# Board_V04.net
KiCad netlist of a schematic drawn in EAGLE
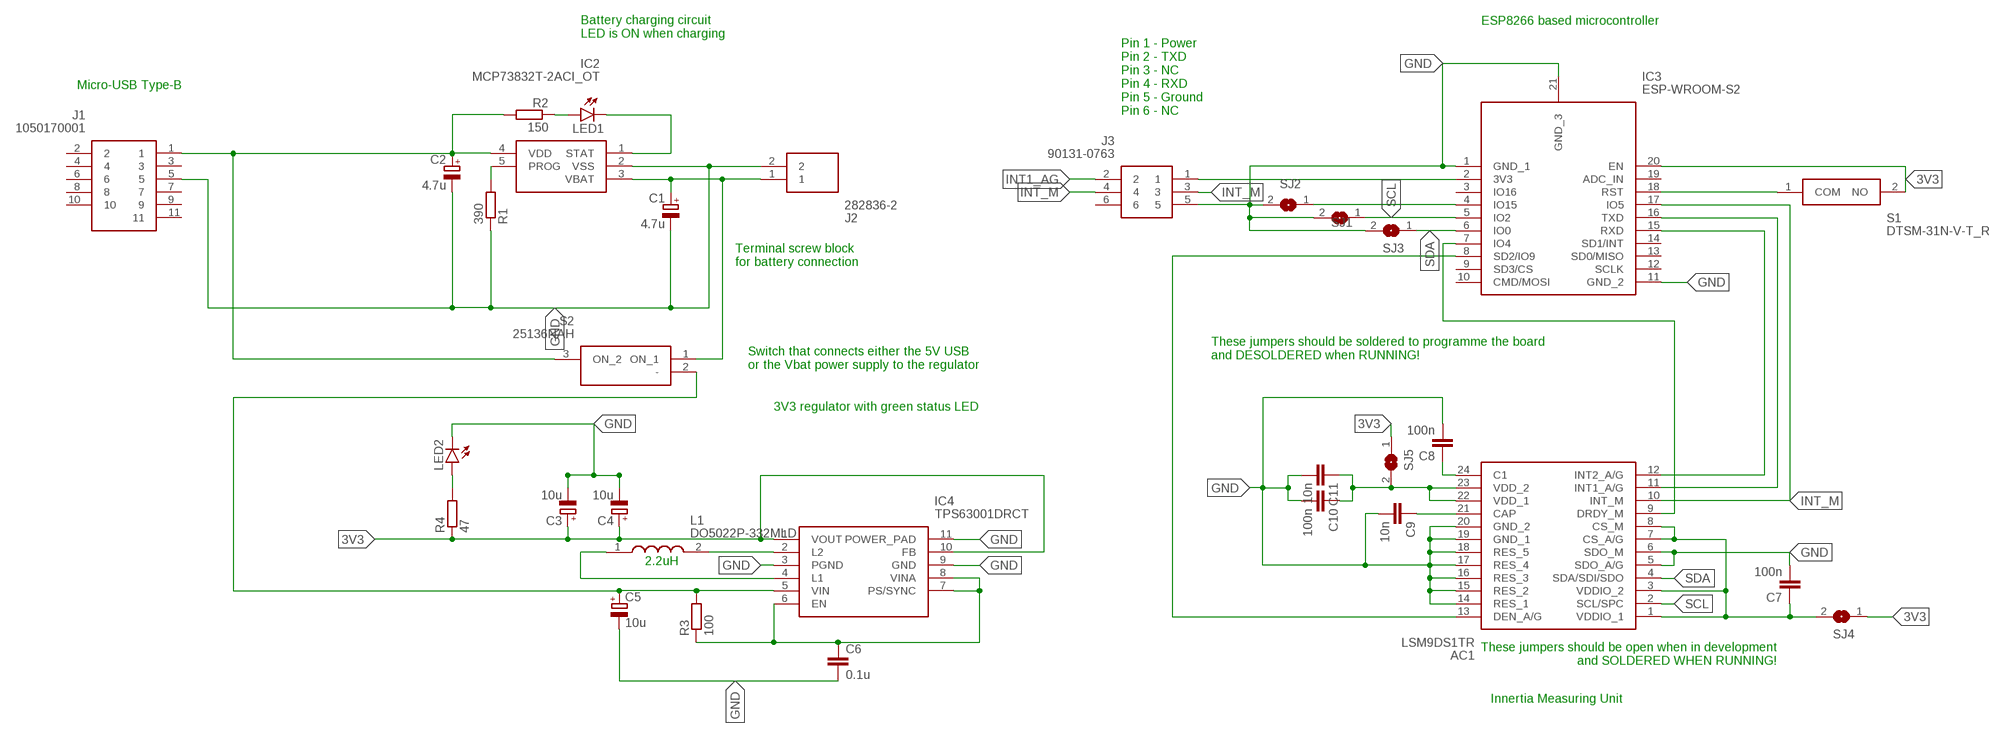
[diagram p0: schematic, sheet 1]

(export (version "E")
  (design (tool "Eeschema 10.0.6"))
  (components
    (comp (ref "AC1")
      (value "LSM9DS1TR")
      (footprint "eagle-import:LGA-24L(3X3.5X1MM)")
      (fields (field (name "MOUSER_PART_NUMBER") "511-LSM9DS1TR") (field (name "RS_PART_NUMBER") "1660908"))
      (libsource (lib "eagle-import") (part "LSM9DS1TR"))
    )
    (comp (ref "C1")
      (value "4.7u")
      (footprint "eagle-import:D_7343-31R")
      (libsource (lib "eagle-import") (part "CPOL-EUD/7343-31R"))
    )
    (comp (ref "C2")
      (value "4.7u")
      (footprint "eagle-import:D_7343-31R")
      (libsource (lib "eagle-import") (part "CPOL-EUD/7343-31R"))
    )
    (comp (ref "C3")
      (value "10u")
      (footprint "eagle-import:D_7343-31R")
      (libsource (lib "eagle-import") (part "CPOL-EUD/7343-31R"))
    )
    (comp (ref "C4")
      (value "10u")
      (footprint "eagle-import:D_7343-31R")
      (libsource (lib "eagle-import") (part "CPOL-EUD/7343-31R"))
    )
    (comp (ref "C5")
      (value "10u")
      (footprint "eagle-import:D_7343-31R")
      (libsource (lib "eagle-import") (part "CPOL-EUD/7343-31R"))
    )
    (comp (ref "C6")
      (value "0.1u")
      (footprint "eagle-import:C0402")
      (libsource (lib "eagle-import") (part "C-EUC0402"))
    )
    (comp (ref "C7")
      (value "100n")
      (footprint "eagle-import:C0805")
      (libsource (lib "eagle-import") (part "C-EUC0805"))
    )
    (comp (ref "C8")
      (value "100n")
      (footprint "eagle-import:C0805")
      (libsource (lib "eagle-import") (part "C-EUC0805"))
    )
    (comp (ref "C9")
      (value "10n")
      (footprint "eagle-import:C0805")
      (libsource (lib "eagle-import") (part "C-EUC0805"))
    )
    (comp (ref "C10")
      (value "100n")
      (footprint "eagle-import:C0805")
      (libsource (lib "eagle-import") (part "C-EUC0805"))
    )
    (comp (ref "C11")
      (value "10n")
      (footprint "eagle-import:C0805")
      (libsource (lib "eagle-import") (part "C-EUC0805"))
    )
    (comp (ref "IC2")
      (value "MCP73832T-2ACI_OT")
      (footprint "eagle-import:SOT95P270X145-5N")
      (fields
        (field (name "MANUFACTURER_PART_NUMBER") "MCP73832T-2ACI/OT")
        (field (name "MOUSER_PART_NUMBER") "579-MCP73832T-2ACIOT")
        (field (name "RS_PART_NUMBER") "9122897")
      )
      (libsource (lib "eagle-import") (part "MCP73832T-2ACI_OT"))
    )
    (comp (ref "IC3")
      (value "ESP-WROOM-S2")
      (footprint "eagle-import:QFN150P1600X1700X315-21N")
      (libsource (lib "eagle-import") (part "ESP-WROOM-S2"))
    )
    (comp (ref "IC4")
      (value "TPS63001DRCT")
      (footprint "eagle-import:SON50P300X300X100-11N")
      (fields (field (name "RS_PART_NUMBER") "7968405"))
      (libsource (lib "eagle-import") (part "TPS63001DRCT"))
    )
    (comp (ref "J1")
      (value "1050170001")
      (footprint "eagle-import:MICROUSB-BTYPE")
      (libsource (lib "eagle-import") (part "1050170001"))
    )
    (comp (ref "J2")
      (value "282836-2")
      (footprint "eagle-import:SHDR2W100P0X500_1X2_1000X820X1")
      (fields (field (name "MOUSER_PART_NUMBER") "571-2828362") (field (name "RS_PART_NUMBER") "1354983"))
      (libsource (lib "eagle-import") (part "282836-2"))
    )
    (comp (ref "J3")
      (value "90131-0763")
      (footprint "eagle-import:HDRV6W90P254_2X3_762X500X560P")
      (fields (field (name "MOUSER_PART_NUMBER") "538-90131-0763") (field (name "RS_PART_NUMBER") "3606443P"))
      (libsource (lib "eagle-import") (part "90131-0763"))
    )
    (comp (ref "L1")
      (value "DO5022P-332MLD")
      (footprint "eagle-import:DO5022P-104MLD")
      (fields (field (name "MOUSER_PART_NUMBER") "994-DO5022P-332MLD"))
      (libsource (lib "eagle-import") (part "DO5022P-332MLD"))
    )
    (comp (ref "LED1")
      (value "LED5MM")
      (footprint "eagle-import:LED5MM")
      (libsource (lib "eagle-import") (part "LED5MM"))
    )
    (comp (ref "LED2")
      (value "LED5MM")
      (footprint "eagle-import:LED5MM")
      (libsource (lib "eagle-import") (part "LED5MM"))
    )
    (comp (ref "R1")
      (value "390")
      (footprint "eagle-import:R0805")
      (libsource (lib "eagle-import") (part "R-EU_R0805"))
    )
    (comp (ref "R2")
      (value "150")
      (footprint "eagle-import:R0805")
      (libsource (lib "eagle-import") (part "R-EU_R0805"))
    )
    (comp (ref "R3")
      (value "100")
      (footprint "eagle-import:R0805")
      (libsource (lib "eagle-import") (part "R-EU_R0805"))
    )
    (comp (ref "R4")
      (value "47")
      (footprint "eagle-import:R0805")
      (libsource (lib "eagle-import") (part "R-EU_R0805"))
    )
    (comp (ref "S1")
      (value "DTSM-31N-V-T_R")
      (footprint "eagle-import:DTSM32NVTR")
      (fields
        (field (name "MANUFACTURER_PART_NUMBER") "DTSM-31N-V-T/R")
        (field (name "MOUSER_PART_NUMBER") "113-DTSM31NVTR")
      )
      (libsource (lib "eagle-import") (part "DTSM-31N-V-T_R"))
    )
    (comp (ref "S2")
      (value "25136NAH")
      (footprint "eagle-import:25136NAH")
      (fields (field (name "MOUSER_PART_NUMBER") "642-25136NAH") (field (name "RS_PART_NUMBER") "0339673A"))
      (libsource (lib "eagle-import") (part "25136NAH"))
    )
    (comp (ref "SJ1")
      (value "SJW")
      (footprint "eagle-import:SJW")
      (libsource (lib "eagle-import") (part "SJW"))
    )
    (comp (ref "SJ2")
      (value "SJW")
      (footprint "eagle-import:SJW")
      (libsource (lib "eagle-import") (part "SJW"))
    )
    (comp (ref "SJ3")
      (value "SJW")
      (footprint "eagle-import:SJW")
      (libsource (lib "eagle-import") (part "SJW"))
    )
    (comp (ref "SJ4")
      (value "SJW")
      (footprint "eagle-import:SJW")
      (libsource (lib "eagle-import") (part "SJW"))
    )
    (comp (ref "SJ5")
      (value "SJW")
      (footprint "eagle-import:SJW")
      (libsource (lib "eagle-import") (part "SJW"))
    )
  )
  (nets
    (net (code "1") (name "3V3") (class "Default")
      (node (ref "C3") (pin "+") (pinfunction "+_+") (pintype "passive"))
      (node (ref "C4") (pin "+") (pinfunction "+_+") (pintype "passive"))
      (node (ref "IC3") (pin "2") (pinfunction "3V3_2") (pintype "power_in"))
      (node (ref "IC3") (pin "20") (pinfunction "EN_20") (pintype "bidirectional"))
      (node (ref "IC4") (pin "1") (pinfunction "VOUT_1") (pintype "bidirectional"))
      (node (ref "IC4") (pin "10") (pinfunction "FB_10") (pintype "bidirectional"))
      (node (ref "J3") (pin "1") (pinfunction "1_1") (pintype "bidirectional"))
      (node (ref "R4") (pin "1") (pinfunction "1_1") (pintype "passive"))
      (node (ref "S1") (pin "2") (pinfunction "NO_2") (pintype "bidirectional"))
      (node (ref "SJ4") (pin "1") (pinfunction "1_1") (pintype "passive"))
      (node (ref "SJ5") (pin "1") (pinfunction "1_1") (pintype "passive"))
    )
    (net (code "2") (name "GND") (class "Default")
      (node (ref "AC1") (pin "14") (pinfunction "RES_1_14") (pintype "power_in"))
      (node (ref "AC1") (pin "15") (pinfunction "RES_2_15") (pintype "power_in"))
      (node (ref "AC1") (pin "16") (pinfunction "RES_3_16") (pintype "power_in"))
      (node (ref "AC1") (pin "17") (pinfunction "RES_4_17") (pintype "power_in"))
      (node (ref "AC1") (pin "18") (pinfunction "RES_5_18") (pintype "power_in"))
      (node (ref "AC1") (pin "19") (pinfunction "GND_1_19") (pintype "power_in"))
      (node (ref "AC1") (pin "20") (pinfunction "GND_2_20") (pintype "power_in"))
      (node (ref "AC1") (pin "5") (pinfunction "SDO_A/G_5") (pintype "output"))
      (node (ref "AC1") (pin "6") (pinfunction "SDO_M_6") (pintype "output"))
      (node (ref "C1") (pin "-") (pinfunction "-_-") (pintype "passive"))
      (node (ref "C10") (pin "2") (pinfunction "2_2") (pintype "passive"))
      (node (ref "C11") (pin "2") (pinfunction "2_2") (pintype "passive"))
      (node (ref "C2") (pin "-") (pinfunction "-_-") (pintype "passive"))
      (node (ref "C3") (pin "-") (pinfunction "-_-") (pintype "passive"))
      (node (ref "C4") (pin "-") (pinfunction "-_-") (pintype "passive"))
      (node (ref "C5") (pin "-") (pinfunction "-_-") (pintype "passive"))
      (node (ref "C6") (pin "2") (pinfunction "2_2") (pintype "passive"))
      (node (ref "C7") (pin "2") (pinfunction "2_2") (pintype "passive"))
      (node (ref "C8") (pin "2") (pinfunction "2_2") (pintype "passive"))
      (node (ref "C9") (pin "2") (pinfunction "2_2") (pintype "passive"))
      (node (ref "IC2") (pin "2") (pinfunction "VSS_2") (pintype "power_in"))
      (node (ref "IC3") (pin "1") (pinfunction "GND_1_1") (pintype "power_in"))
      (node (ref "IC3") (pin "11") (pinfunction "GND_2_11") (pintype "power_in"))
      (node (ref "IC3") (pin "21") (pinfunction "GND_3_21") (pintype "power_in"))
      (node (ref "IC4") (pin "11") (pinfunction "POWER_PAD_11") (pintype "bidirectional"))
      (node (ref "IC4") (pin "3") (pinfunction "PGND_3") (pintype "bidirectional"))
      (node (ref "IC4") (pin "9") (pinfunction "GND_9") (pintype "bidirectional"))
      (node (ref "J1") (pin "5") (pinfunction "5_5") (pintype "bidirectional"))
      (node (ref "J2") (pin "2") (pinfunction "2_2") (pintype "bidirectional"))
      (node (ref "J3") (pin "5") (pinfunction "5_5") (pintype "bidirectional"))
      (node (ref "LED2") (pin "K") (pinfunction "C_K") (pintype "passive"))
      (node (ref "R1") (pin "1") (pinfunction "1_1") (pintype "passive"))
      (node (ref "SJ1") (pin "2") (pinfunction "2_2") (pintype "passive"))
      (node (ref "SJ2") (pin "2") (pinfunction "2_2") (pintype "passive"))
      (node (ref "SJ3") (pin "2") (pinfunction "2_2") (pintype "passive"))
    )
    (net (code "3") (name "INT1_AG") (class "Default")
      (node (ref "AC1") (pin "11") (pinfunction "INT1_A/G_11") (pintype "bidirectional"))
      (node (ref "IC3") (pin "16") (pinfunction "TXD_16") (pintype "bidirectional"))
      (node (ref "J3") (pin "2") (pinfunction "2_2") (pintype "bidirectional"))
    )
    (net (code "4") (name "INT_M") (class "Default")
      (node (ref "AC1") (pin "10") (pinfunction "INT_M_10") (pintype "bidirectional"))
      (node (ref "IC3") (pin "17") (pinfunction "IO5_17") (pintype "bidirectional"))
      (node (ref "J3") (pin "3") (pinfunction "3_3") (pintype "bidirectional"))
      (node (ref "J3") (pin "4") (pinfunction "4_4") (pintype "bidirectional"))
    )
    (net (code "5") (name "Net-(AC1-C1)") (class "Default")
      (node (ref "AC1") (pin "24") (pinfunction "C1_24") (pintype "bidirectional"))
      (node (ref "C8") (pin "1") (pinfunction "1_1") (pintype "passive"))
    )
    (net (code "6") (name "Net-(AC1-CAP)") (class "Default")
      (node (ref "AC1") (pin "21") (pinfunction "CAP_21") (pintype "power_in"))
      (node (ref "C9") (pin "1") (pinfunction "1_1") (pintype "passive"))
    )
    (net (code "7") (name "Net-(AC1-CS_A{slash}G)") (class "Default")
      (node (ref "AC1") (pin "1") (pinfunction "VDDIO_1_1") (pintype "power_in"))
      (node (ref "AC1") (pin "3") (pinfunction "VDDIO_2_3") (pintype "power_in"))
      (node (ref "AC1") (pin "7") (pinfunction "CS_A/G_7") (pintype "bidirectional"))
      (node (ref "AC1") (pin "8") (pinfunction "CS_M_8") (pintype "bidirectional"))
      (node (ref "C7") (pin "1") (pinfunction "1_1") (pintype "passive"))
      (node (ref "SJ4") (pin "2") (pinfunction "2_2") (pintype "passive"))
    )
    (net (code "8") (name "Net-(AC1-DEN_A{slash}G)") (class "Default")
      (node (ref "AC1") (pin "13") (pinfunction "DEN_A/G_13") (pintype "bidirectional"))
      (node (ref "IC3") (pin "8") (pinfunction "SD2/IO9_8") (pintype "bidirectional"))
    )
    (net (code "9") (name "Net-(AC1-DRDY_M)") (class "Default")
      (node (ref "AC1") (pin "9") (pinfunction "DRDY_M_9") (pintype "bidirectional"))
      (node (ref "IC3") (pin "7") (pinfunction "IO4_7") (pintype "bidirectional"))
    )
    (net (code "10") (name "Net-(AC1-INT2_A{slash}G)") (class "Default")
      (node (ref "AC1") (pin "12") (pinfunction "INT2_A/G_12") (pintype "bidirectional"))
      (node (ref "IC3") (pin "15") (pinfunction "RXD_15") (pintype "bidirectional"))
    )
    (net (code "11") (name "Net-(AC1-VDD_1)") (class "Default")
      (node (ref "AC1") (pin "22") (pinfunction "VDD_1_22") (pintype "power_in"))
      (node (ref "AC1") (pin "23") (pinfunction "VDD_2_23") (pintype "power_in"))
      (node (ref "C10") (pin "1") (pinfunction "1_1") (pintype "passive"))
      (node (ref "C11") (pin "1") (pinfunction "1_1") (pintype "passive"))
      (node (ref "SJ5") (pin "2") (pinfunction "2_2") (pintype "passive"))
    )
    (net (code "12") (name "Net-(IC2-PROG)") (class "Default")
      (node (ref "IC2") (pin "5") (pinfunction "PROG_5") (pintype "bidirectional"))
      (node (ref "R1") (pin "2") (pinfunction "2_2") (pintype "passive"))
    )
    (net (code "13") (name "Net-(IC2-STAT)") (class "Default")
      (node (ref "IC2") (pin "1") (pinfunction "STAT_1") (pintype "bidirectional"))
      (node (ref "LED1") (pin "K") (pinfunction "C_K") (pintype "passive"))
    )
    (net (code "14") (name "Net-(IC2-VBAT)") (class "Default")
      (node (ref "C1") (pin "+") (pinfunction "+_+") (pintype "passive"))
      (node (ref "IC2") (pin "3") (pinfunction "VBAT_3") (pintype "bidirectional"))
      (node (ref "J2") (pin "1") (pinfunction "1_1") (pintype "bidirectional"))
      (node (ref "S2") (pin "1") (pinfunction "ON_1_1") (pintype "bidirectional"))
    )
    (net (code "15") (name "Net-(IC2-VDD)") (class "Default")
      (node (ref "C2") (pin "+") (pinfunction "+_+") (pintype "passive"))
      (node (ref "IC2") (pin "4") (pinfunction "VDD_4") (pintype "power_in"))
      (node (ref "J1") (pin "1") (pinfunction "1_1") (pintype "bidirectional"))
      (node (ref "R2") (pin "2") (pinfunction "2_2") (pintype "passive"))
      (node (ref "S2") (pin "3") (pinfunction "ON_2_3") (pintype "bidirectional"))
    )
    (net (code "16") (name "Net-(IC3-IO15)") (class "Default")
      (node (ref "IC3") (pin "4") (pinfunction "IO15_4") (pintype "bidirectional"))
      (node (ref "SJ2") (pin "1") (pinfunction "1_1") (pintype "passive"))
    )
    (net (code "17") (name "Net-(IC3-RST)") (class "Default")
      (node (ref "IC3") (pin "18") (pinfunction "RST_18") (pintype "input"))
      (node (ref "S1") (pin "1") (pinfunction "COM_1") (pintype "bidirectional"))
    )
    (net (code "18") (name "Net-(IC4-EN)") (class "Default")
      (node (ref "C6") (pin "1") (pinfunction "1_1") (pintype "passive"))
      (node (ref "IC4") (pin "6") (pinfunction "EN_6") (pintype "bidirectional"))
      (node (ref "IC4") (pin "7") (pinfunction "PS/SYNC_7") (pintype "bidirectional"))
      (node (ref "IC4") (pin "8") (pinfunction "VINA_8") (pintype "bidirectional"))
      (node (ref "R3") (pin "1") (pinfunction "1_1") (pintype "passive"))
    )
    (net (code "19") (name "Net-(IC4-L1)") (class "Default")
      (node (ref "IC4") (pin "4") (pinfunction "L1_4") (pintype "bidirectional"))
      (node (ref "L1") (pin "1") (pinfunction "1_1") (pintype "bidirectional"))
    )
    (net (code "20") (name "Net-(IC4-L2)") (class "Default")
      (node (ref "IC4") (pin "2") (pinfunction "L2_2") (pintype "bidirectional"))
      (node (ref "L1") (pin "2") (pinfunction "2_2") (pintype "bidirectional"))
    )
    (net (code "21") (name "Net-(IC4-VIN)") (class "Default")
      (node (ref "C5") (pin "+") (pinfunction "+_+") (pintype "passive"))
      (node (ref "IC4") (pin "5") (pinfunction "VIN_5") (pintype "bidirectional"))
      (node (ref "R3") (pin "2") (pinfunction "2_2") (pintype "passive"))
      (node (ref "S2") (pin "2") (pinfunction "-_2") (pintype "bidirectional"))
    )
    (net (code "22") (name "Net-(LED1-PadA)") (class "Default")
      (node (ref "LED1") (pin "A") (pinfunction "A_A") (pintype "passive"))
      (node (ref "R2") (pin "1") (pinfunction "1_1") (pintype "passive"))
    )
    (net (code "23") (name "Net-(LED2-PadA)") (class "Default")
      (node (ref "LED2") (pin "A") (pinfunction "A_A") (pintype "passive"))
      (node (ref "R4") (pin "2") (pinfunction "2_2") (pintype "passive"))
    )
    (net (code "24") (name "SCL") (class "Default")
      (node (ref "AC1") (pin "2") (pinfunction "SCL/SPC_2") (pintype "output"))
      (node (ref "IC3") (pin "5") (pinfunction "IO2_5") (pintype "bidirectional"))
      (node (ref "SJ1") (pin "1") (pinfunction "1_1") (pintype "passive"))
    )
    (net (code "25") (name "SDA") (class "Default")
      (node (ref "AC1") (pin "4") (pinfunction "SDA/SDI/SDO_4") (pintype "bidirectional"))
      (node (ref "IC3") (pin "6") (pinfunction "IO0_6") (pintype "bidirectional"))
      (node (ref "SJ3") (pin "1") (pinfunction "1_1") (pintype "passive"))
    )
    (net (code "26") (name "unconnected-(IC3-ADC_IN-Pad19)") (class "Default")
      (node (ref "IC3") (pin "19") (pinfunction "ADC_IN_19") (pintype "input"))
    )
    (net (code "27") (name "unconnected-(IC3-CMD{slash}MOSI-Pad10)") (class "Default")
      (node (ref "IC3") (pin "10") (pinfunction "CMD/MOSI_10") (pintype "bidirectional"))
    )
    (net (code "28") (name "unconnected-(IC3-IO16-Pad3)") (class "Default")
      (node (ref "IC3") (pin "3") (pinfunction "IO16_3") (pintype "bidirectional"))
    )
    (net (code "29") (name "unconnected-(IC3-SCLK-Pad12)") (class "Default")
      (node (ref "IC3") (pin "12") (pinfunction "SCLK_12") (pintype "bidirectional"))
    )
    (net (code "30") (name "unconnected-(IC3-SD0{slash}MISO-Pad13)") (class "Default")
      (node (ref "IC3") (pin "13") (pinfunction "SD0/MISO_13") (pintype "bidirectional"))
    )
    (net (code "31") (name "unconnected-(IC3-SD1{slash}INT-Pad14)") (class "Default")
      (node (ref "IC3") (pin "14") (pinfunction "SD1/INT_14") (pintype "bidirectional"))
    )
    (net (code "32") (name "unconnected-(IC3-SD3{slash}CS-Pad9)") (class "Default")
      (node (ref "IC3") (pin "9") (pinfunction "SD3/CS_9") (pintype "bidirectional"))
    )
    (net (code "33") (name "unconnected-(J1-Pad2)") (class "Default")
      (node (ref "J1") (pin "2") (pinfunction "2_2") (pintype "bidirectional"))
    )
    (net (code "34") (name "unconnected-(J1-Pad3)") (class "Default")
      (node (ref "J1") (pin "3") (pinfunction "3_3") (pintype "bidirectional"))
    )
    (net (code "35") (name "unconnected-(J1-Pad4)") (class "Default")
      (node (ref "J1") (pin "4") (pinfunction "4_4") (pintype "bidirectional"))
    )
    (net (code "36") (name "unconnected-(J1-Pad6)") (class "Default")
      (node (ref "J1") (pin "6") (pinfunction "6_6") (pintype "bidirectional"))
    )
    (net (code "37") (name "unconnected-(J1-Pad7)") (class "Default")
      (node (ref "J1") (pin "7") (pinfunction "7_7") (pintype "bidirectional"))
    )
    (net (code "38") (name "unconnected-(J1-Pad8)") (class "Default")
      (node (ref "J1") (pin "8") (pinfunction "8_8") (pintype "bidirectional"))
    )
    (net (code "39") (name "unconnected-(J1-Pad9)") (class "Default")
      (node (ref "J1") (pin "9") (pinfunction "9_9") (pintype "bidirectional"))
    )
    (net (code "40") (name "unconnected-(J1-Pad10)") (class "Default")
      (node (ref "J1") (pin "10") (pinfunction "10_10") (pintype "bidirectional"))
    )
    (net (code "41") (name "unconnected-(J1-Pad11)") (class "Default")
      (node (ref "J1") (pin "11") (pinfunction "11_11") (pintype "bidirectional"))
    )
    (net (code "42") (name "unconnected-(J3-Pad6)") (class "Default")
      (node (ref "J3") (pin "6") (pinfunction "6_6") (pintype "bidirectional"))
    )
  )
)
